# AAS_module_Touch-rev1_2.net
KiCad netlist of a schematic drawn in Altium Designer
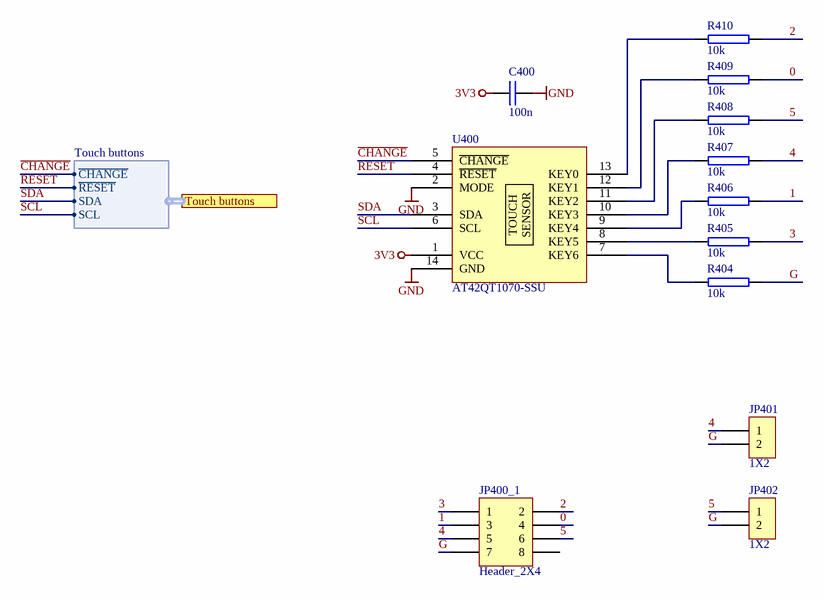
[diagram p0: AAS_module_Touch-rev1_2.SchDoc]

(export (version "E")
  (design (tool "Eeschema 10.0.6"))
  (components
    (comp (ref "C400")
      (value "100n")
      (footprint "C0603")
      (description "Capacitor SMD 0603")
      (libsource (lib "SmartSys") (part "C_0603"))
    )
    (comp (ref "JP400_1")
      (value "Header_2X4")
      (footprint "HDR2X4")
      (description "Header dual row")
      (libsource (lib "ELEKON") (part "Header2X4"))
    )
    (comp (ref "JP401")
      (value "1X2")
      (footprint "HDR1X2")
      (description "Header, 2-Pin, Single row")
      (libsource (lib "SmartSys") (part "Header 1X2"))
    )
    (comp (ref "JP402")
      (value "1X2")
      (footprint "HDR1X2")
      (description "Header, 2-Pin, Single row")
      (libsource (lib "SmartSys") (part "Header 1X2"))
    )
    (comp (ref "R404")
      (value "10k")
      (footprint "R0603")
      (description "Resistor SMD 0603")
      (libsource (lib "SmartSys") (part "R_0603"))
    )
    (comp (ref "R405")
      (value "10k")
      (footprint "R0603")
      (description "Resistor SMD 0603")
      (libsource (lib "SmartSys") (part "R_0603"))
    )
    (comp (ref "R406")
      (value "10k")
      (footprint "R0603")
      (description "Resistor SMD 0603")
      (libsource (lib "SmartSys") (part "R_0603"))
    )
    (comp (ref "R407")
      (value "10k")
      (footprint "R0603")
      (description "Resistor SMD 0603")
      (libsource (lib "SmartSys") (part "R_0603"))
    )
    (comp (ref "R408")
      (value "10k")
      (footprint "R0603")
      (description "Resistor SMD 0603")
      (libsource (lib "SmartSys") (part "R_0603"))
    )
    (comp (ref "R409")
      (value "10k")
      (footprint "R0603")
      (description "Resistor SMD 0603")
      (libsource (lib "SmartSys") (part "R_0603"))
    )
    (comp (ref "R410")
      (value "10k")
      (footprint "R0603")
      (description "Resistor SMD 0603")
      (libsource (lib "SmartSys") (part "R_0603"))
    )
    (comp (ref "U400")
      (value "AT42QT1070-SSU")
      (footprint "SO-14")
      (description "Seven-channel QTouch® Touch Sensor IC")
      (libsource (lib "my_parts") (part "AT42QT1070-SSU"))
    )
  )
  (nets
    (net (code "3") (name "/0") (class "Default")
      (node (ref "JP400_1") (pin "4") (pinfunction "4_4") (pintype "passive"))
      (node (ref "R409") (pin "2") (pinfunction "2_2") (pintype "passive"))
    )
    (net (code "4") (name "/1") (class "Default")
      (node (ref "JP400_1") (pin "3") (pinfunction "3_3") (pintype "passive"))
      (node (ref "R406") (pin "2") (pinfunction "2_2") (pintype "passive"))
    )
    (net (code "5") (name "/2") (class "Default")
      (node (ref "JP400_1") (pin "2") (pinfunction "2_2") (pintype "passive"))
      (node (ref "R410") (pin "2") (pinfunction "2_2") (pintype "passive"))
    )
    (net (code "6") (name "/3") (class "Default")
      (node (ref "JP400_1") (pin "1") (pinfunction "1_1") (pintype "passive"))
      (node (ref "R405") (pin "2") (pinfunction "2_2") (pintype "passive"))
    )
    (net (code "7") (name "/4") (class "Default")
      (node (ref "JP400_1") (pin "5") (pinfunction "5_5") (pintype "passive"))
      (node (ref "JP401") (pin "1") (pinfunction "1_1") (pintype "passive"))
      (node (ref "R407") (pin "2") (pinfunction "2_2") (pintype "passive"))
    )
    (net (code "8") (name "/5") (class "Default")
      (node (ref "JP400_1") (pin "6") (pinfunction "6_6") (pintype "passive"))
      (node (ref "JP402") (pin "1") (pinfunction "1_1") (pintype "passive"))
      (node (ref "R408") (pin "2") (pinfunction "2_2") (pintype "passive"))
    )
    (net (code "9") (name "/G") (class "Default")
      (node (ref "JP400_1") (pin "7") (pinfunction "7_7") (pintype "passive"))
      (node (ref "JP401") (pin "2") (pinfunction "2_2") (pintype "passive"))
      (node (ref "JP402") (pin "2") (pinfunction "2_2") (pintype "passive"))
      (node (ref "R404") (pin "2") (pinfunction "2_2") (pintype "passive"))
    )
    (net (code "10") (name "/SCL") (class "Default")
      (node (ref "U400") (pin "6") (pinfunction "SCL_6") (pintype "passive"))
    )
    (net (code "11") (name "/SDA") (class "Default")
      (node (ref "U400") (pin "3") (pinfunction "SDA_3") (pintype "passive"))
    )
    (net (code "13") (name "/~{CHANGE}") (class "Default")
      (node (ref "U400") (pin "5") (pinfunction "~{CHANGE}_5") (pintype "passive"))
    )
    (net (code "14") (name "/~{RESET}") (class "Default")
      (node (ref "U400") (pin "4") (pinfunction "~{RESET}_4") (pintype "passive"))
    )
    (net (code "15") (name "3V3") (class "Default")
      (node (ref "C400") (pin "1") (pinfunction "1_1") (pintype "passive"))
      (node (ref "U400") (pin "1") (pinfunction "VCC_1") (pintype "passive"))
    )
    (net (code "16") (name "GND") (class "Default")
      (node (ref "C400") (pin "2") (pinfunction "2_2") (pintype "passive"))
      (node (ref "U400") (pin "14") (pinfunction "GND_14") (pintype "passive"))
      (node (ref "U400") (pin "2") (pinfunction "MODE_2") (pintype "passive"))
    )
    (net (code "17") (name "Net-(U400-KEY0)") (class "Default")
      (node (ref "R410") (pin "1") (pinfunction "1_1") (pintype "passive"))
      (node (ref "U400") (pin "13") (pinfunction "KEY0_13") (pintype "passive"))
    )
    (net (code "18") (name "Net-(U400-KEY1)") (class "Default")
      (node (ref "R409") (pin "1") (pinfunction "1_1") (pintype "passive"))
      (node (ref "U400") (pin "12") (pinfunction "KEY1_12") (pintype "passive"))
    )
    (net (code "19") (name "Net-(U400-KEY2)") (class "Default")
      (node (ref "R408") (pin "1") (pinfunction "1_1") (pintype "passive"))
      (node (ref "U400") (pin "11") (pinfunction "KEY2_11") (pintype "passive"))
    )
    (net (code "20") (name "Net-(U400-KEY3)") (class "Default")
      (node (ref "R407") (pin "1") (pinfunction "1_1") (pintype "passive"))
      (node (ref "U400") (pin "10") (pinfunction "KEY3_10") (pintype "passive"))
    )
    (net (code "21") (name "Net-(U400-KEY4)") (class "Default")
      (node (ref "R406") (pin "1") (pinfunction "1_1") (pintype "passive"))
      (node (ref "U400") (pin "9") (pinfunction "KEY4_9") (pintype "passive"))
    )
    (net (code "22") (name "Net-(U400-KEY5)") (class "Default")
      (node (ref "R405") (pin "1") (pinfunction "1_1") (pintype "passive"))
      (node (ref "U400") (pin "8") (pinfunction "KEY5_8") (pintype "passive"))
    )
    (net (code "23") (name "Net-(U400-KEY6)") (class "Default")
      (node (ref "R404") (pin "1") (pinfunction "1_1") (pintype "passive"))
      (node (ref "U400") (pin "7") (pinfunction "KEY6_7") (pintype "passive"))
    )
    (net (code "24") (name "unconnected-(JP400_1-Pad8)") (class "Default")
      (node (ref "JP400_1") (pin "8") (pinfunction "8_8") (pintype "passive"))
    )
  )
)
